# Power.net
KiCad netlist of a schematic drawn in Altium Designer
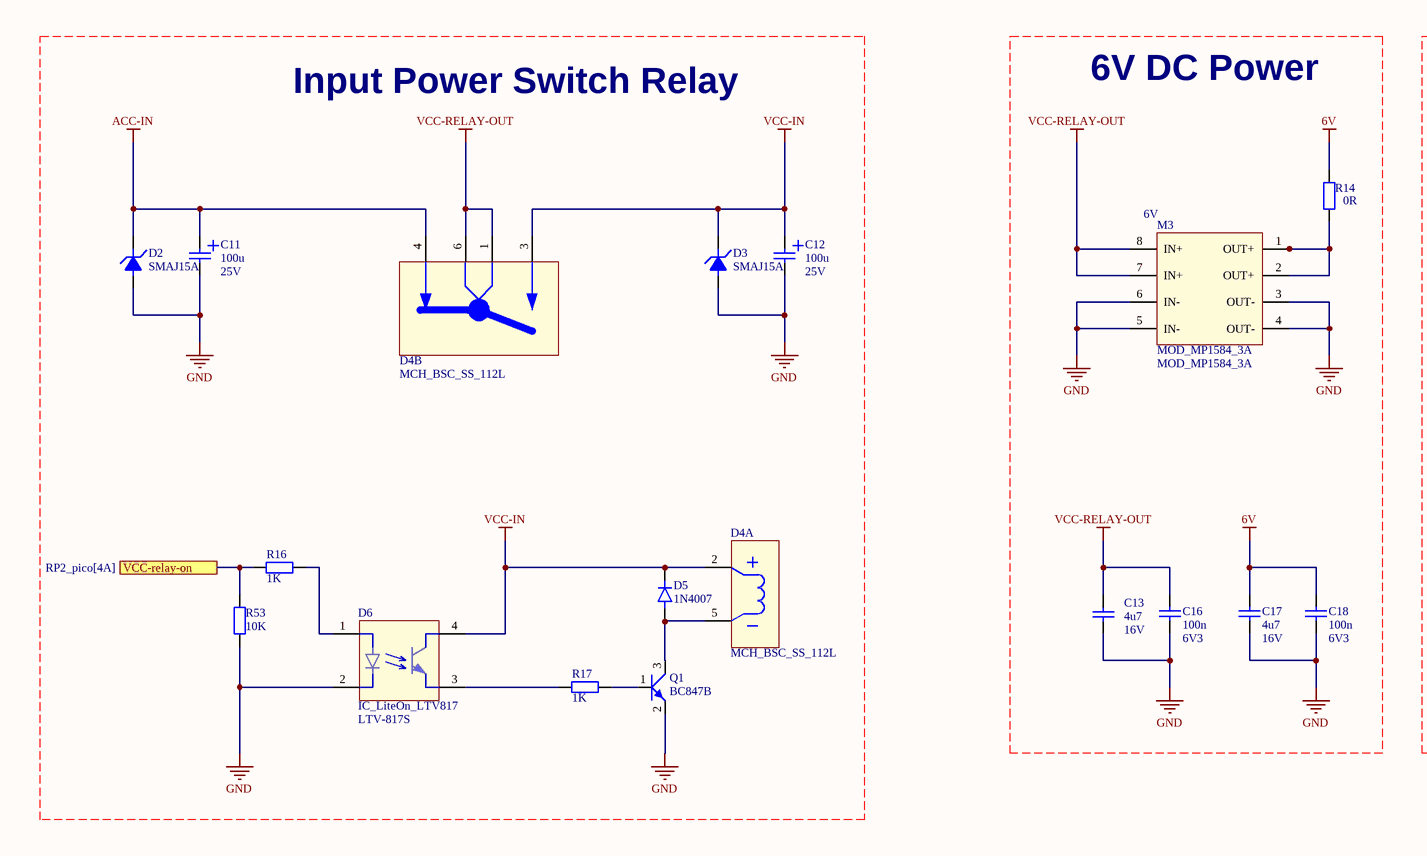
[diagram p0: Power.SchDoc, left]
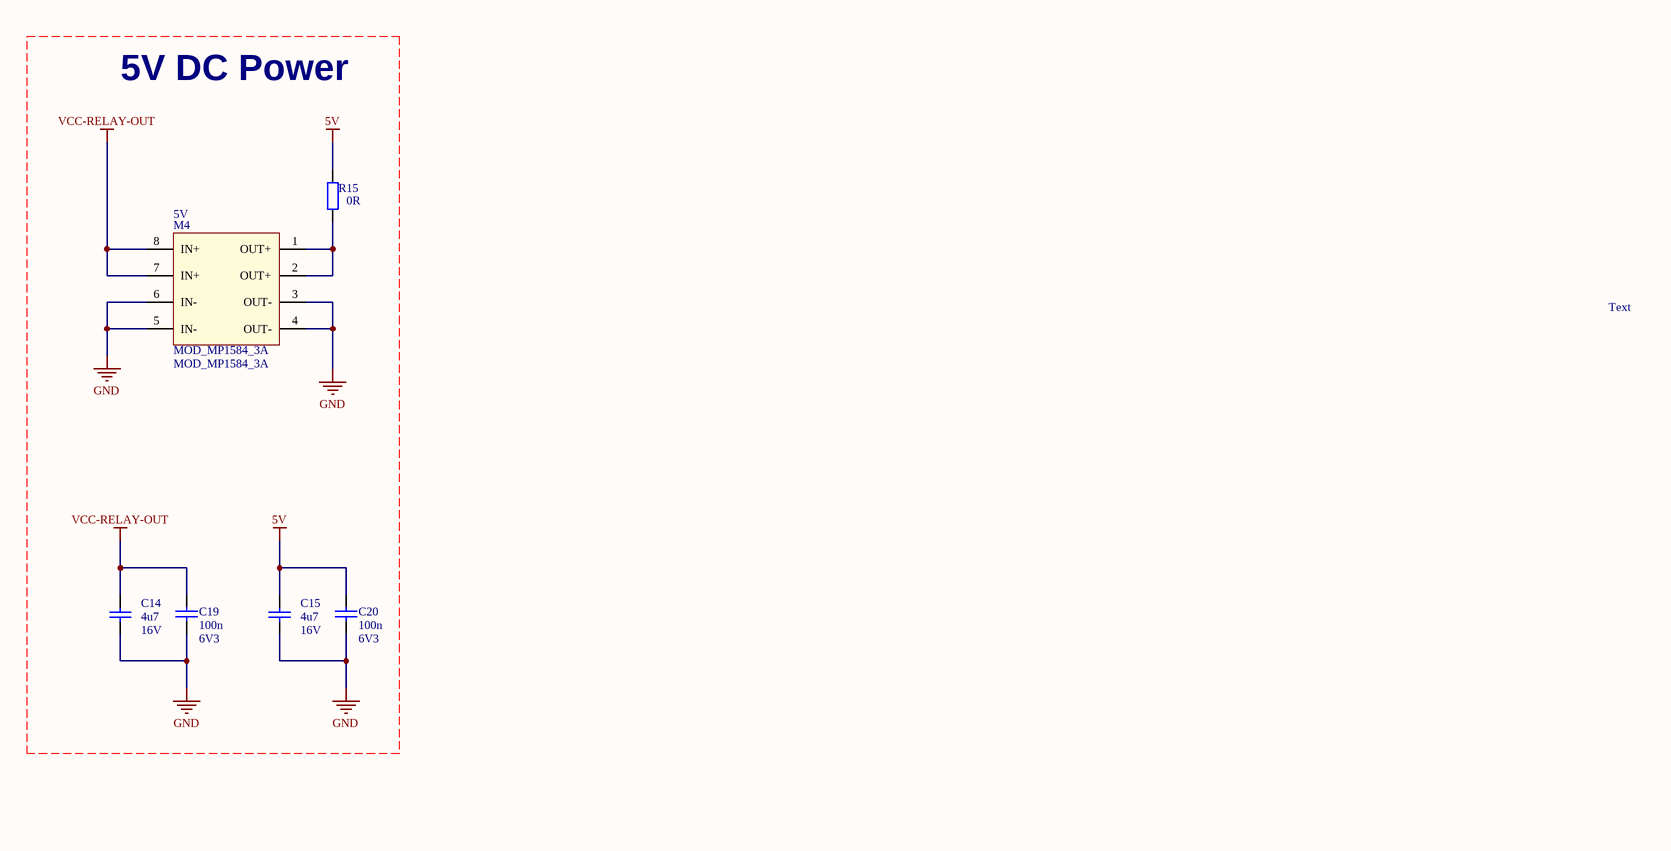
[diagram p1: Power.SchDoc, right]

(export (version "E")
  (design (tool "Eeschema 10.0.6"))
  (components
    (comp (ref "C11")
      (value "CAP_POL")
      (footprint "CAPAE9983X102N")
      (description "PANASONIC - EEEFC1E101AP - CAP, ALU ELEC, 100UF, 25V, SMD, REEL")
      (fields
        (field (name "VALUE1") "100u")
        (field (name "VALUE2") "25V")
        (field (name "MANUFACTURER") "Panasonic")
      )
      (libsource (lib "DSW_Lib") (part "CAP_POL"))
    )
    (comp (ref "C12")
      (value "CAP_POL")
      (footprint "CAPAE9983X102N")
      (description "PANASONIC - EEEFC1E101AP - CAP, ALU ELEC, 100UF, 25V, SMD, REEL")
      (fields
        (field (name "VALUE1") "100u")
        (field (name "VALUE2") "25V")
        (field (name "MANUFACTURER") "Panasonic")
      )
      (libsource (lib "DSW_Lib") (part "CAP_POL"))
    )
    (comp (ref "C13")
      (value "CAP")
      (footprint "CAPC2012X140N")
      (description "X7R 10% 0805")
      (fields
        (field (name "VALUE1") "4u7")
        (field (name "VALUE2") "16V")
        (field (name "MANUFACTURER") "MURATA")
      )
      (libsource (lib "DSW_Lib") (part "CAP"))
    )
    (comp (ref "C14")
      (value "CAP")
      (footprint "CAPC2012X140N")
      (description "X7R 10% 0805")
      (fields
        (field (name "VALUE1") "4u7")
        (field (name "VALUE2") "16V")
        (field (name "MANUFACTURER") "MURATA")
      )
      (libsource (lib "DSW_Lib") (part "CAP"))
    )
    (comp (ref "C15")
      (value "CAP")
      (footprint "CAPC2012X140N")
      (description "X7R 10% 0805")
      (fields
        (field (name "VALUE1") "4u7")
        (field (name "VALUE2") "16V")
        (field (name "MANUFACTURER") "MURATA")
      )
      (libsource (lib "DSW_Lib") (part "CAP"))
    )
    (comp (ref "C16")
      (value "CAP")
      (footprint "CAPC2012X88N")
      (description "X7R 10% 0805")
      (fields
        (field (name "VALUE1") "100n")
        (field (name "VALUE2") "6V3")
        (field (name "MANUFACTURER") "KEMET")
      )
      (libsource (lib "DSW_Lib") (part "CAP"))
    )
    (comp (ref "C17")
      (value "CAP")
      (footprint "CAPC2012X140N")
      (description "X7R 10% 0805")
      (fields
        (field (name "VALUE1") "4u7")
        (field (name "VALUE2") "16V")
        (field (name "MANUFACTURER") "MURATA")
      )
      (libsource (lib "DSW_Lib") (part "CAP"))
    )
    (comp (ref "C18")
      (value "CAP")
      (footprint "CAPC2012X88N")
      (description "X7R 10% 0805")
      (fields
        (field (name "VALUE1") "100n")
        (field (name "VALUE2") "6V3")
        (field (name "MANUFACTURER") "KEMET")
      )
      (libsource (lib "DSW_Lib") (part "CAP"))
    )
    (comp (ref "C19")
      (value "CAP")
      (footprint "CAPC2012X88N")
      (description "X7R 10% 0805")
      (fields
        (field (name "VALUE1") "100n")
        (field (name "VALUE2") "6V3")
        (field (name "MANUFACTURER") "KEMET")
      )
      (libsource (lib "DSW_Lib") (part "CAP"))
    )
    (comp (ref "C20")
      (value "CAP")
      (footprint "CAPC2012X88N")
      (description "X7R 10% 0805")
      (fields
        (field (name "VALUE1") "100n")
        (field (name "VALUE2") "6V3")
        (field (name "MANUFACTURER") "KEMET")
      )
      (libsource (lib "DSW_Lib") (part "CAP"))
    )
    (comp (ref "D2")
      (value "DIO_UNIDIRECTIONAL_TVS")
      (footprint "DO-214AC")
      (description "Transient Voltage Suppressors")
      (fields (field (name "VALUE1") "SMAJ15A") (field (name "MANUFACTURER") "Littelfuse"))
      (libsource (lib "DSW_Lib") (part "DIO_UNIDIRECTIONAL_TVS"))
    )
    (comp (ref "D3")
      (value "DIO_UNIDIRECTIONAL_TVS")
      (footprint "DO-214AC")
      (description "Transient Voltage Suppressors")
      (fields (field (name "VALUE1") "SMAJ15A") (field (name "MANUFACTURER") "Littelfuse"))
      (libsource (lib "DSW_Lib") (part "DIO_UNIDIRECTIONAL_TVS"))
    )
    (comp (ref "D4")
      (value "MCH_BSC_SS_112L")
      (footprint "MCH_BSC_SS_112L")
      (description "Small relay 6 pins 12V, 2A")
      (fields (field (name "MANUFACTURER") "KJS"))
      (libsource (lib "DSW_Lib") (part "MCH_BSC_SS_112L"))
    )
    (comp (ref "D5")
      (value "DIO")
      (footprint "DO-214AC")
      (description "M7 Diode, max 30A")
      (fields (field (name "VALUE1") "1N4007"))
      (libsource (lib "DSW_Lib") (part "DIO"))
    )
    (comp (ref "D6")
      (value "IC_LiteOn_LTV817")
      (footprint "IC_LiteOn_ LTV-817S")
      (description "Transistor Output Optocouplers Optocoupler Phototrans")
      (fields (field (name "VALUE1") "LTV-817S") (field (name "MANUFACTURER") "Lite-On"))
      (libsource (lib "DSW_Lib") (part "IC_LiteOn_LTV817"))
    )
    (comp (ref "M3")
      (value "MOD_MP1584_3A")
      (footprint "MOD_MP1584_3A")
      (description "DC-DC converter 3A")
      (fields (field (name "VALUE1") "MOD_MP1584_3A") (field (name "MANUFACTURER") "CH"))
      (libsource (lib "DSW_Lib") (part "MOD_MP1584_3A"))
    )
    (comp (ref "M4")
      (value "MOD_MP1584_3A")
      (footprint "MOD_MP1584_3A")
      (description "DC-DC converter 3A")
      (fields (field (name "VALUE1") "MOD_MP1584_3A") (field (name "MANUFACTURER") "CH"))
      (libsource (lib "DSW_Lib") (part "MOD_MP1584_3A"))
    )
    (comp (ref "Q1")
      (value "TRS_NPN_123")
      (footprint "SOT23")
      (description "Bipolar Transistors - BJT NPN 45V 100mA")
      (fields (field (name "VALUE1") "BC847B") (field (name "MANUFACTURER") "NXP"))
      (libsource (lib "DSW_Lib") (part "TRS_NPN_123"))
    )
    (comp (ref "R14")
      (value "RES")
      (footprint "RESC2012X60N")
      (description "Thick Film Resistors - SMD ZERO OHM JUMPER 1/8watt")
      (fields (field (name "VALUE1") "0R") (field (name "MANUFACTURER") "Vishay"))
      (libsource (lib "DSW_Lib") (part "RES"))
    )
    (comp (ref "R15")
      (value "RES")
      (footprint "RESC2012X60N")
      (description "Thick Film Resistors - SMD ZERO OHM JUMPER 1/8watt")
      (fields (field (name "VALUE1") "0R") (field (name "MANUFACTURER") "Vishay"))
      (libsource (lib "DSW_Lib") (part "RES"))
    )
    (comp (ref "R16")
      (value "RES")
      (footprint "RESC2012X60N")
      (description "RESISTOR, 0805, 1K, 1%, SMD")
      (fields (field (name "VALUE1") "1K") (field (name "MANUFACTURER") "Yageo"))
      (libsource (lib "") (part "RES_1"))
    )
    (comp (ref "R17")
      (value "RES")
      (footprint "RESC2012X60N")
      (description "RESISTOR, 0805, 1K, 1%, SMD")
      (fields (field (name "VALUE1") "1K") (field (name "MANUFACTURER") "Yageo"))
      (libsource (lib "") (part "RES_1"))
    )
    (comp (ref "R53")
      (value "RES")
      (footprint "RESC2012X60N")
      (description "RESISTOR, 0805, 10K, 1%, SMD")
      (fields (field (name "VALUE1") "10K") (field (name "MANUFACTURER") "Yageo"))
      (libsource (lib "") (part "RES_2"))
    )
  )
  (nets
    (net (code "1") (name "/VCC-relay-on") (class "Default")
      (node (ref "R16") (pin "2") (pinfunction "2_2") (pintype "passive"))
      (node (ref "R53") (pin "1") (pinfunction "1_1") (pintype "passive"))
    )
    (net (code "2") (name "5V") (class "Default")
      (node (ref "C15") (pin "1") (pinfunction "1_1") (pintype "passive"))
      (node (ref "C20") (pin "2") (pinfunction "2_2") (pintype "passive"))
      (node (ref "R15") (pin "2") (pinfunction "2_2") (pintype "passive"))
    )
    (net (code "3") (name "6V") (class "Default")
      (node (ref "C17") (pin "2") (pinfunction "2_2") (pintype "passive"))
      (node (ref "C18") (pin "2") (pinfunction "2_2") (pintype "passive"))
      (node (ref "R14") (pin "2") (pinfunction "2_2") (pintype "passive"))
    )
    (net (code "4") (name "ACC-IN") (class "Default")
      (node (ref "C11") (pin "1") (pinfunction "1_1") (pintype "passive"))
      (node (ref "D2") (pin "2") (pinfunction "2_2") (pintype "passive"))
      (node (ref "D4") (pin "4") (pinfunction "4_4") (pintype "passive"))
    )
    (net (code "5") (name "GND") (class "Default")
      (node (ref "C11") (pin "2") (pinfunction "2_2") (pintype "passive"))
      (node (ref "C12") (pin "2") (pinfunction "2_2") (pintype "passive"))
      (node (ref "C13") (pin "2") (pinfunction "2_2") (pintype "passive"))
      (node (ref "C14") (pin "2") (pinfunction "2_2") (pintype "passive"))
      (node (ref "C15") (pin "2") (pinfunction "2_2") (pintype "passive"))
      (node (ref "C16") (pin "1") (pinfunction "1_1") (pintype "passive"))
      (node (ref "C17") (pin "1") (pinfunction "1_1") (pintype "passive"))
      (node (ref "C18") (pin "1") (pinfunction "1_1") (pintype "passive"))
      (node (ref "C19") (pin "1") (pinfunction "1_1") (pintype "passive"))
      (node (ref "C20") (pin "1") (pinfunction "1_1") (pintype "passive"))
      (node (ref "D2") (pin "1") (pinfunction "1_1") (pintype "passive"))
      (node (ref "D3") (pin "1") (pinfunction "1_1") (pintype "passive"))
      (node (ref "D6") (pin "2") (pinfunction "2_2") (pintype "passive"))
      (node (ref "M3") (pin "3") (pinfunction "OUT-_3") (pintype "power_in"))
      (node (ref "M3") (pin "4") (pinfunction "OUT-_4") (pintype "power_in"))
      (node (ref "M3") (pin "5") (pinfunction "IN-_5") (pintype "power_in"))
      (node (ref "M3") (pin "6") (pinfunction "IN-_6") (pintype "power_in"))
      (node (ref "M4") (pin "3") (pinfunction "OUT-_3") (pintype "power_in"))
      (node (ref "M4") (pin "4") (pinfunction "OUT-_4") (pintype "power_in"))
      (node (ref "M4") (pin "5") (pinfunction "IN-_5") (pintype "power_in"))
      (node (ref "M4") (pin "6") (pinfunction "IN-_6") (pintype "power_in"))
      (node (ref "Q1") (pin "2") (pinfunction "E_2") (pintype "passive"))
      (node (ref "R53") (pin "2") (pinfunction "2_2") (pintype "passive"))
    )
    (net (code "6") (name "Net-(D5-A)") (class "Default")
      (node (ref "D4") (pin "5") (pinfunction "5_5") (pintype "passive"))
      (node (ref "D5") (pin "1") (pinfunction "A_1") (pintype "passive"))
      (node (ref "Q1") (pin "3") (pinfunction "C_3") (pintype "passive"))
    )
    (net (code "7") (name "Net-(D6-Pad1)") (class "Default")
      (node (ref "D6") (pin "1") (pinfunction "1_1") (pintype "passive"))
      (node (ref "R16") (pin "1") (pinfunction "1_1") (pintype "passive"))
    )
    (net (code "8") (name "Net-(D6-Pad3)") (class "Default")
      (node (ref "D6") (pin "3") (pinfunction "3_3") (pintype "passive"))
      (node (ref "R17") (pin "2") (pinfunction "2_2") (pintype "passive"))
    )
    (net (code "9") (name "Net-(M3-OUT+-Pad1)") (class "Default")
      (node (ref "M3") (pin "1") (pinfunction "OUT+_1") (pintype "power_in"))
      (node (ref "M3") (pin "2") (pinfunction "OUT+_2") (pintype "power_in"))
      (node (ref "R14") (pin "1") (pinfunction "1_1") (pintype "passive"))
    )
    (net (code "10") (name "Net-(M4-OUT+-Pad1)") (class "Default")
      (node (ref "M4") (pin "1") (pinfunction "OUT+_1") (pintype "power_in"))
      (node (ref "M4") (pin "2") (pinfunction "OUT+_2") (pintype "power_in"))
      (node (ref "R15") (pin "1") (pinfunction "1_1") (pintype "passive"))
    )
    (net (code "11") (name "Net-(Q1-B)") (class "Default")
      (node (ref "Q1") (pin "1") (pinfunction "B_1") (pintype "passive"))
      (node (ref "R17") (pin "1") (pinfunction "1_1") (pintype "passive"))
    )
    (net (code "12") (name "VCC-IN") (class "Default")
      (node (ref "C12") (pin "1") (pinfunction "1_1") (pintype "passive"))
      (node (ref "D3") (pin "2") (pinfunction "2_2") (pintype "passive"))
      (node (ref "D4") (pin "2") (pinfunction "2_2") (pintype "passive"))
      (node (ref "D4") (pin "3") (pinfunction "3_3") (pintype "passive"))
      (node (ref "D5") (pin "2") (pinfunction "K_2") (pintype "passive"))
      (node (ref "D6") (pin "4") (pinfunction "4_4") (pintype "passive"))
    )
    (net (code "13") (name "VCC-RELAY-OUT") (class "Default")
      (node (ref "C13") (pin "1") (pinfunction "1_1") (pintype "passive"))
      (node (ref "C14") (pin "1") (pinfunction "1_1") (pintype "passive"))
      (node (ref "C16") (pin "2") (pinfunction "2_2") (pintype "passive"))
      (node (ref "C19") (pin "2") (pinfunction "2_2") (pintype "passive"))
      (node (ref "D4") (pin "1") (pinfunction "1_1") (pintype "passive"))
      (node (ref "D4") (pin "6") (pinfunction "6_6") (pintype "passive"))
      (node (ref "M3") (pin "7") (pinfunction "IN+_7") (pintype "power_in"))
      (node (ref "M3") (pin "8") (pinfunction "IN+_8") (pintype "power_in"))
      (node (ref "M4") (pin "7") (pinfunction "IN+_7") (pintype "power_in"))
      (node (ref "M4") (pin "8") (pinfunction "IN+_8") (pintype "power_in"))
    )
  )
)
